# fpga01-serdes-power.net
KiCad netlist of a schematic drawn in Altium Designer
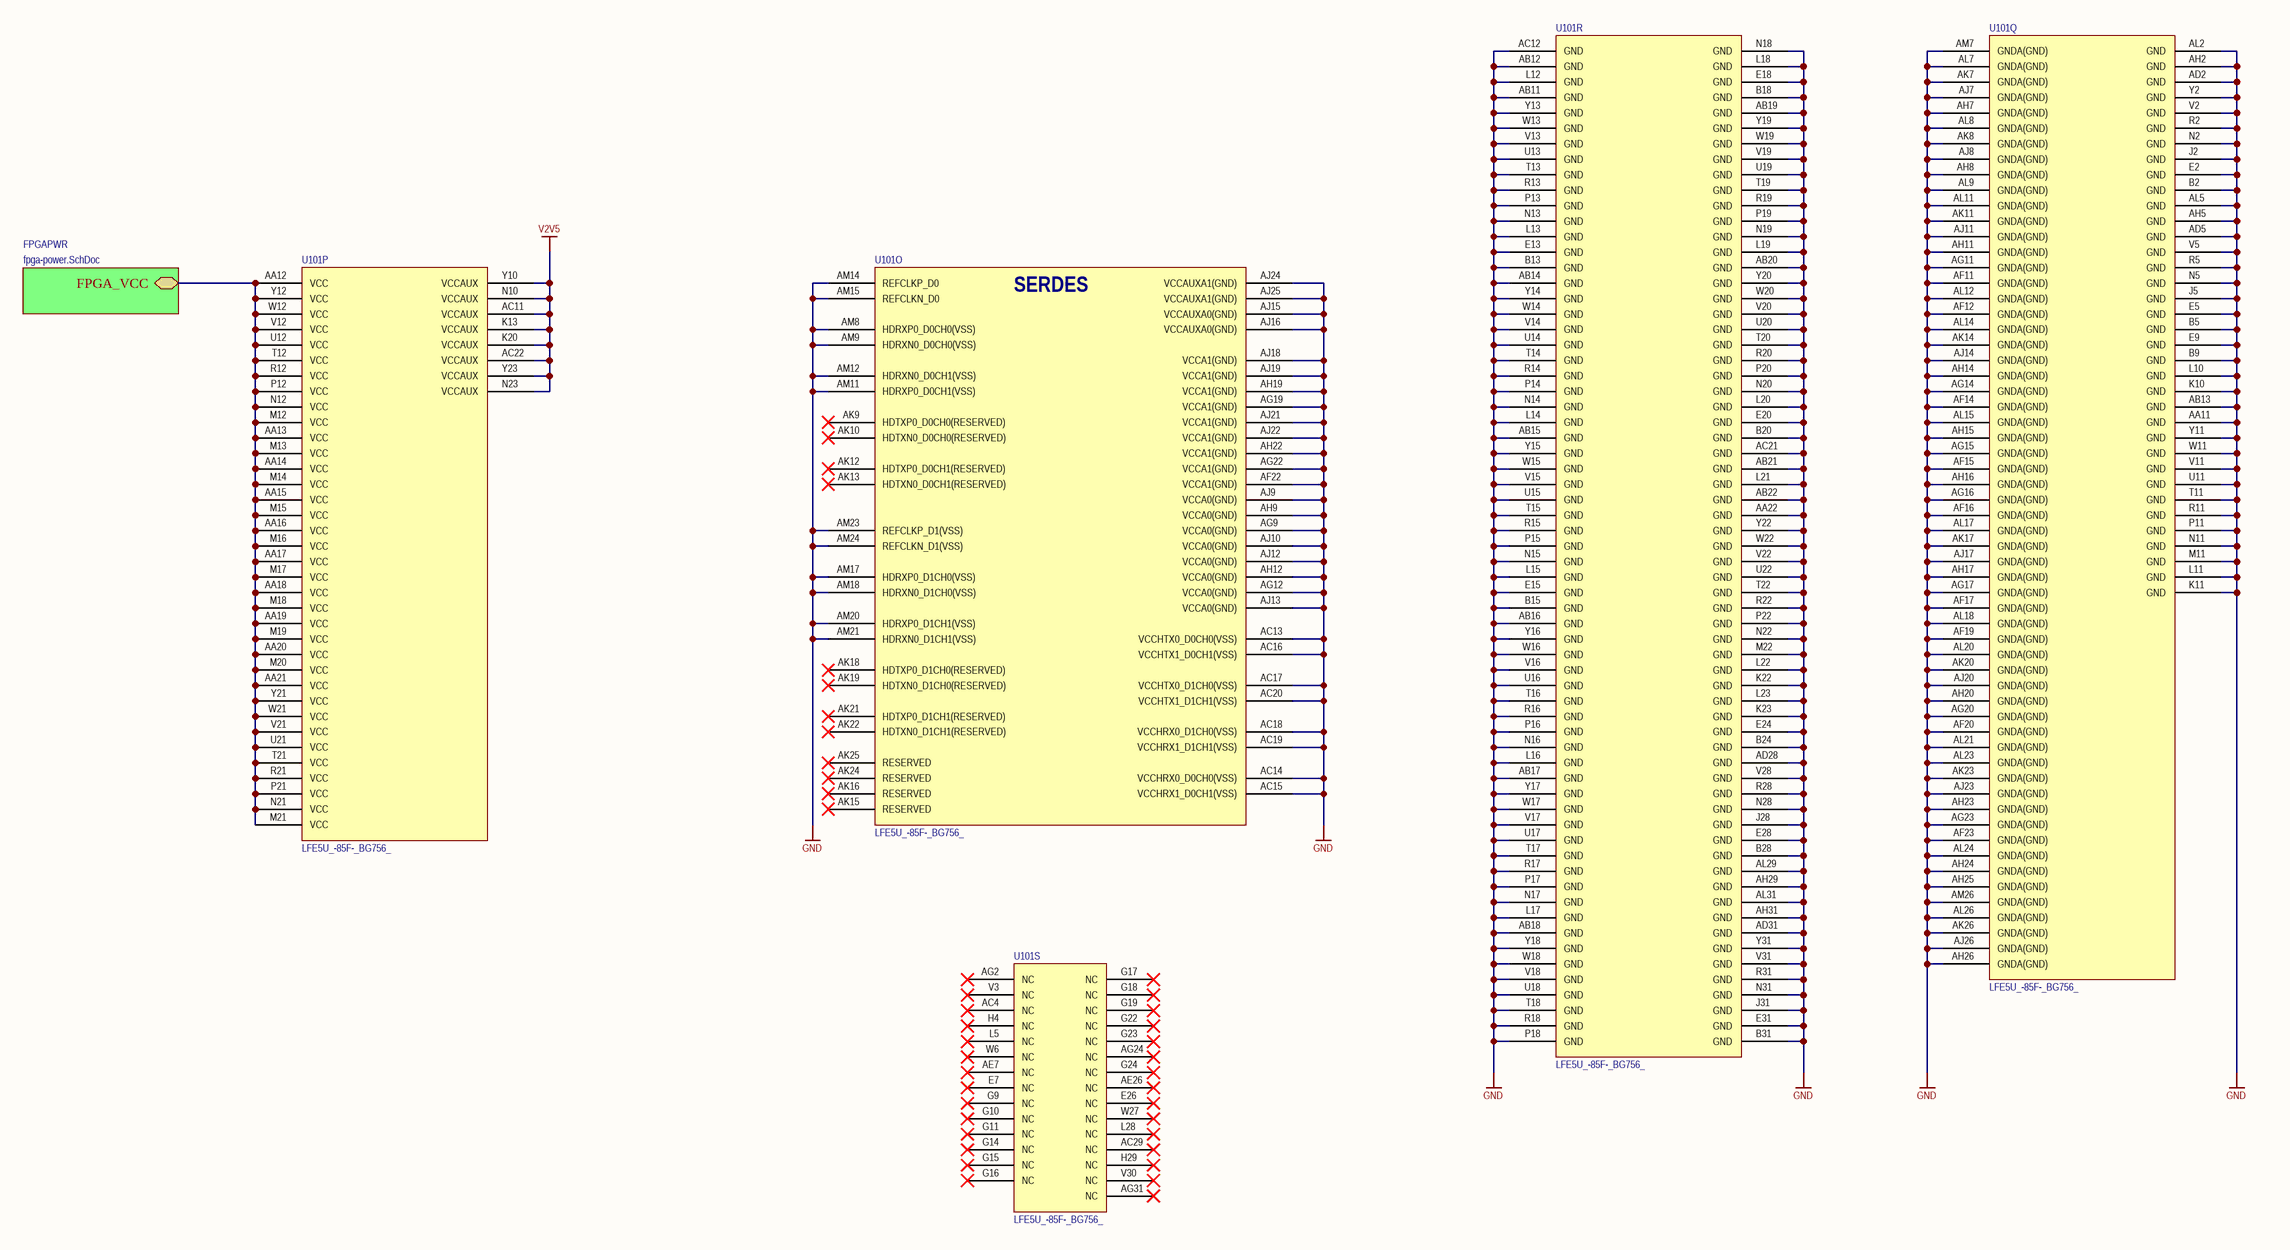
[diagram p0: fpga01-serdes-power.SchDoc]

(export (version "E")
  (design (tool "Eeschema 10.0.6"))
  (components
    (comp (ref "U101")
      (value "LFE5U_-85F-_BG756_")
      (footprint "lattice:caBGA756")
      (description "ECP5 FPGA, 85k LUT, 756-caBGA")
      (fields (field (name "MANUFACTURER") "Lattice Semiconductor"))
      (libsource (lib "lattice") (part "LFE5U_-85F-_BG756_"))
    )
  )
  (nets
    (net (code "1") (name "/FPGA_VCC") (class "Default")
      (node (ref "U101") (pin "AA12") (pinfunction "VCC_AA12") (pintype "power_in"))
      (node (ref "U101") (pin "AA13") (pinfunction "VCC_AA13") (pintype "power_in"))
      (node (ref "U101") (pin "AA14") (pinfunction "VCC_AA14") (pintype "power_in"))
      (node (ref "U101") (pin "AA15") (pinfunction "VCC_AA15") (pintype "power_in"))
      (node (ref "U101") (pin "AA16") (pinfunction "VCC_AA16") (pintype "power_in"))
      (node (ref "U101") (pin "AA17") (pinfunction "VCC_AA17") (pintype "power_in"))
      (node (ref "U101") (pin "AA18") (pinfunction "VCC_AA18") (pintype "power_in"))
      (node (ref "U101") (pin "AA19") (pinfunction "VCC_AA19") (pintype "power_in"))
      (node (ref "U101") (pin "AA20") (pinfunction "VCC_AA20") (pintype "power_in"))
      (node (ref "U101") (pin "AA21") (pinfunction "VCC_AA21") (pintype "power_in"))
      (node (ref "U101") (pin "M12") (pinfunction "VCC_M12") (pintype "power_in"))
      (node (ref "U101") (pin "M13") (pinfunction "VCC_M13") (pintype "power_in"))
      (node (ref "U101") (pin "M14") (pinfunction "VCC_M14") (pintype "power_in"))
      (node (ref "U101") (pin "M15") (pinfunction "VCC_M15") (pintype "power_in"))
      (node (ref "U101") (pin "M16") (pinfunction "VCC_M16") (pintype "power_in"))
      (node (ref "U101") (pin "M17") (pinfunction "VCC_M17") (pintype "power_in"))
      (node (ref "U101") (pin "M18") (pinfunction "VCC_M18") (pintype "power_in"))
      (node (ref "U101") (pin "M19") (pinfunction "VCC_M19") (pintype "power_in"))
      (node (ref "U101") (pin "M20") (pinfunction "VCC_M20") (pintype "power_in"))
      (node (ref "U101") (pin "M21") (pinfunction "VCC_M21") (pintype "power_in"))
      (node (ref "U101") (pin "N12") (pinfunction "VCC_N12") (pintype "power_in"))
      (node (ref "U101") (pin "N21") (pinfunction "VCC_N21") (pintype "power_in"))
      (node (ref "U101") (pin "P12") (pinfunction "VCC_P12") (pintype "power_in"))
      (node (ref "U101") (pin "P21") (pinfunction "VCC_P21") (pintype "power_in"))
      (node (ref "U101") (pin "R12") (pinfunction "VCC_R12") (pintype "power_in"))
      (node (ref "U101") (pin "R21") (pinfunction "VCC_R21") (pintype "power_in"))
      (node (ref "U101") (pin "T12") (pinfunction "VCC_T12") (pintype "power_in"))
      (node (ref "U101") (pin "T21") (pinfunction "VCC_T21") (pintype "power_in"))
      (node (ref "U101") (pin "U12") (pinfunction "VCC_U12") (pintype "power_in"))
      (node (ref "U101") (pin "U21") (pinfunction "VCC_U21") (pintype "power_in"))
      (node (ref "U101") (pin "V12") (pinfunction "VCC_V12") (pintype "power_in"))
      (node (ref "U101") (pin "V21") (pinfunction "VCC_V21") (pintype "power_in"))
      (node (ref "U101") (pin "W12") (pinfunction "VCC_W12") (pintype "power_in"))
      (node (ref "U101") (pin "W21") (pinfunction "VCC_W21") (pintype "power_in"))
      (node (ref "U101") (pin "Y12") (pinfunction "VCC_Y12") (pintype "power_in"))
      (node (ref "U101") (pin "Y21") (pinfunction "VCC_Y21") (pintype "power_in"))
    )
    (net (code "2") (name "GND") (class "Default")
      (node (ref "U101") (pin "AA11") (pinfunction "GND_AA11") (pintype "power_in"))
      (node (ref "U101") (pin "AA22") (pinfunction "GND_AA22") (pintype "power_in"))
      (node (ref "U101") (pin "AB11") (pinfunction "GND_AB11") (pintype "power_in"))
      (node (ref "U101") (pin "AB12") (pinfunction "GND_AB12") (pintype "power_in"))
      (node (ref "U101") (pin "AB13") (pinfunction "GND_AB13") (pintype "power_in"))
      (node (ref "U101") (pin "AB14") (pinfunction "GND_AB14") (pintype "power_in"))
      (node (ref "U101") (pin "AB15") (pinfunction "GND_AB15") (pintype "power_in"))
      (node (ref "U101") (pin "AB16") (pinfunction "GND_AB16") (pintype "power_in"))
      (node (ref "U101") (pin "AB17") (pinfunction "GND_AB17") (pintype "power_in"))
      (node (ref "U101") (pin "AB18") (pinfunction "GND_AB18") (pintype "power_in"))
      (node (ref "U101") (pin "AB19") (pinfunction "GND_AB19") (pintype "power_in"))
      (node (ref "U101") (pin "AB20") (pinfunction "GND_AB20") (pintype "power_in"))
      (node (ref "U101") (pin "AB21") (pinfunction "GND_AB21") (pintype "power_in"))
      (node (ref "U101") (pin "AB22") (pinfunction "GND_AB22") (pintype "power_in"))
      (node (ref "U101") (pin "AC12") (pinfunction "GND_AC12") (pintype "power_in"))
      (node (ref "U101") (pin "AC13") (pinfunction "VCCHTX0_D0CH0(VSS)_AC13") (pintype "power_in"))
      (node (ref "U101") (pin "AC14") (pinfunction "VCCHRX0_D0CH0(VSS)_AC14") (pintype "power_in"))
      (node (ref "U101") (pin "AC15") (pinfunction "VCCHRX1_D0CH1(VSS)_AC15") (pintype "power_in"))
      (node (ref "U101") (pin "AC16") (pinfunction "VCCHTX1_D0CH1(VSS)_AC16") (pintype "power_in"))
      (node (ref "U101") (pin "AC17") (pinfunction "VCCHTX0_D1CH0(VSS)_AC17") (pintype "power_in"))
      (node (ref "U101") (pin "AC18") (pinfunction "VCCHRX0_D1CH0(VSS)_AC18") (pintype "power_in"))
      (node (ref "U101") (pin "AC19") (pinfunction "VCCHRX1_D1CH1(VSS)_AC19") (pintype "power_in"))
      (node (ref "U101") (pin "AC20") (pinfunction "VCCHTX1_D1CH1(VSS)_AC20") (pintype "power_in"))
      (node (ref "U101") (pin "AC21") (pinfunction "GND_AC21") (pintype "power_in"))
      (node (ref "U101") (pin "AD2") (pinfunction "GND_AD2") (pintype "power_in"))
      (node (ref "U101") (pin "AD28") (pinfunction "GND_AD28") (pintype "power_in"))
      (node (ref "U101") (pin "AD31") (pinfunction "GND_AD31") (pintype "power_in"))
      (node (ref "U101") (pin "AD5") (pinfunction "GND_AD5") (pintype "power_in"))
      (node (ref "U101") (pin "AF11") (pinfunction "GNDA(GND)_AF11") (pintype "power_in"))
      (node (ref "U101") (pin "AF12") (pinfunction "GNDA(GND)_AF12") (pintype "power_in"))
      (node (ref "U101") (pin "AF14") (pinfunction "GNDA(GND)_AF14") (pintype "power_in"))
      (node (ref "U101") (pin "AF15") (pinfunction "GNDA(GND)_AF15") (pintype "power_in"))
      (node (ref "U101") (pin "AF16") (pinfunction "GNDA(GND)_AF16") (pintype "power_in"))
      (node (ref "U101") (pin "AF17") (pinfunction "GNDA(GND)_AF17") (pintype "power_in"))
      (node (ref "U101") (pin "AF19") (pinfunction "GNDA(GND)_AF19") (pintype "power_in"))
      (node (ref "U101") (pin "AF20") (pinfunction "GNDA(GND)_AF20") (pintype "power_in"))
      (node (ref "U101") (pin "AF22") (pinfunction "VCCA1(GND)_AF22") (pintype "power_in"))
      (node (ref "U101") (pin "AF23") (pinfunction "GNDA(GND)_AF23") (pintype "power_in"))
      (node (ref "U101") (pin "AG11") (pinfunction "GNDA(GND)_AG11") (pintype "power_in"))
      (node (ref "U101") (pin "AG12") (pinfunction "VCCA0(GND)_AG12") (pintype "power_in"))
      (node (ref "U101") (pin "AG14") (pinfunction "GNDA(GND)_AG14") (pintype "power_in"))
      (node (ref "U101") (pin "AG15") (pinfunction "GNDA(GND)_AG15") (pintype "power_in"))
      (node (ref "U101") (pin "AG16") (pinfunction "GNDA(GND)_AG16") (pintype "power_in"))
      (node (ref "U101") (pin "AG17") (pinfunction "GNDA(GND)_AG17") (pintype "power_in"))
      (node (ref "U101") (pin "AG19") (pinfunction "VCCA1(GND)_AG19") (pintype "power_in"))
      (node (ref "U101") (pin "AG20") (pinfunction "GNDA(GND)_AG20") (pintype "power_in"))
      (node (ref "U101") (pin "AG22") (pinfunction "VCCA1(GND)_AG22") (pintype "power_in"))
      (node (ref "U101") (pin "AG23") (pinfunction "GNDA(GND)_AG23") (pintype "power_in"))
      (node (ref "U101") (pin "AG9") (pinfunction "VCCA0(GND)_AG9") (pintype "power_in"))
      (node (ref "U101") (pin "AH11") (pinfunction "GNDA(GND)_AH11") (pintype "power_in"))
      (node (ref "U101") (pin "AH12") (pinfunction "VCCA0(GND)_AH12") (pintype "power_in"))
      (node (ref "U101") (pin "AH14") (pinfunction "GNDA(GND)_AH14") (pintype "power_in"))
      (node (ref "U101") (pin "AH15") (pinfunction "GNDA(GND)_AH15") (pintype "power_in"))
      (node (ref "U101") (pin "AH16") (pinfunction "GNDA(GND)_AH16") (pintype "power_in"))
      (node (ref "U101") (pin "AH17") (pinfunction "GNDA(GND)_AH17") (pintype "power_in"))
      (node (ref "U101") (pin "AH19") (pinfunction "VCCA1(GND)_AH19") (pintype "power_in"))
      (node (ref "U101") (pin "AH2") (pinfunction "GND_AH2") (pintype "power_in"))
      (node (ref "U101") (pin "AH20") (pinfunction "GNDA(GND)_AH20") (pintype "power_in"))
      (node (ref "U101") (pin "AH22") (pinfunction "VCCA1(GND)_AH22") (pintype "power_in"))
      (node (ref "U101") (pin "AH23") (pinfunction "GNDA(GND)_AH23") (pintype "power_in"))
      (node (ref "U101") (pin "AH24") (pinfunction "GNDA(GND)_AH24") (pintype "power_in"))
      (node (ref "U101") (pin "AH25") (pinfunction "GNDA(GND)_AH25") (pintype "power_in"))
      (node (ref "U101") (pin "AH26") (pinfunction "GNDA(GND)_AH26") (pintype "power_in"))
      (node (ref "U101") (pin "AH29") (pinfunction "GND_AH29") (pintype "power_in"))
      (node (ref "U101") (pin "AH31") (pinfunction "GND_AH31") (pintype "power_in"))
      (node (ref "U101") (pin "AH5") (pinfunction "GND_AH5") (pintype "power_in"))
      (node (ref "U101") (pin "AH7") (pinfunction "GNDA(GND)_AH7") (pintype "power_in"))
      (node (ref "U101") (pin "AH8") (pinfunction "GNDA(GND)_AH8") (pintype "power_in"))
      (node (ref "U101") (pin "AH9") (pinfunction "VCCA0(GND)_AH9") (pintype "power_in"))
      (node (ref "U101") (pin "AJ10") (pinfunction "VCCA0(GND)_AJ10") (pintype "power_in"))
      (node (ref "U101") (pin "AJ11") (pinfunction "GNDA(GND)_AJ11") (pintype "power_in"))
      (node (ref "U101") (pin "AJ12") (pinfunction "VCCA0(GND)_AJ12") (pintype "power_in"))
      (node (ref "U101") (pin "AJ13") (pinfunction "VCCA0(GND)_AJ13") (pintype "power_in"))
      (node (ref "U101") (pin "AJ14") (pinfunction "GNDA(GND)_AJ14") (pintype "power_in"))
      (node (ref "U101") (pin "AJ15") (pinfunction "VCCAUXA0(GND)_AJ15") (pintype "power_in"))
      (node (ref "U101") (pin "AJ16") (pinfunction "VCCAUXA0(GND)_AJ16") (pintype "power_in"))
      (node (ref "U101") (pin "AJ17") (pinfunction "GNDA(GND)_AJ17") (pintype "power_in"))
      (node (ref "U101") (pin "AJ18") (pinfunction "VCCA1(GND)_AJ18") (pintype "power_in"))
      (node (ref "U101") (pin "AJ19") (pinfunction "VCCA1(GND)_AJ19") (pintype "power_in"))
      (node (ref "U101") (pin "AJ20") (pinfunction "GNDA(GND)_AJ20") (pintype "power_in"))
      (node (ref "U101") (pin "AJ21") (pinfunction "VCCA1(GND)_AJ21") (pintype "power_in"))
      (node (ref "U101") (pin "AJ22") (pinfunction "VCCA1(GND)_AJ22") (pintype "power_in"))
      (node (ref "U101") (pin "AJ23") (pinfunction "GNDA(GND)_AJ23") (pintype "power_in"))
      (node (ref "U101") (pin "AJ24") (pinfunction "VCCAUXA1(GND)_AJ24") (pintype "power_in"))
      (node (ref "U101") (pin "AJ25") (pinfunction "VCCAUXA1(GND)_AJ25") (pintype "power_in"))
      (node (ref "U101") (pin "AJ26") (pinfunction "GNDA(GND)_AJ26") (pintype "power_in"))
      (node (ref "U101") (pin "AJ7") (pinfunction "GNDA(GND)_AJ7") (pintype "power_in"))
      (node (ref "U101") (pin "AJ8") (pinfunction "GNDA(GND)_AJ8") (pintype "power_in"))
      (node (ref "U101") (pin "AJ9") (pinfunction "VCCA0(GND)_AJ9") (pintype "power_in"))
      (node (ref "U101") (pin "AK11") (pinfunction "GNDA(GND)_AK11") (pintype "power_in"))
      (node (ref "U101") (pin "AK14") (pinfunction "GNDA(GND)_AK14") (pintype "power_in"))
      (node (ref "U101") (pin "AK17") (pinfunction "GNDA(GND)_AK17") (pintype "power_in"))
      (node (ref "U101") (pin "AK20") (pinfunction "GNDA(GND)_AK20") (pintype "power_in"))
      (node (ref "U101") (pin "AK23") (pinfunction "GNDA(GND)_AK23") (pintype "power_in"))
      (node (ref "U101") (pin "AK26") (pinfunction "GNDA(GND)_AK26") (pintype "power_in"))
      (node (ref "U101") (pin "AK7") (pinfunction "GNDA(GND)_AK7") (pintype "power_in"))
      (node (ref "U101") (pin "AK8") (pinfunction "GNDA(GND)_AK8") (pintype "power_in"))
      (node (ref "U101") (pin "AL11") (pinfunction "GNDA(GND)_AL11") (pintype "power_in"))
      (node (ref "U101") (pin "AL12") (pinfunction "GNDA(GND)_AL12") (pintype "power_in"))
      (node (ref "U101") (pin "AL14") (pinfunction "GNDA(GND)_AL14") (pintype "power_in"))
      (node (ref "U101") (pin "AL15") (pinfunction "GNDA(GND)_AL15") (pintype "power_in"))
      (node (ref "U101") (pin "AL17") (pinfunction "GNDA(GND)_AL17") (pintype "power_in"))
      (node (ref "U101") (pin "AL18") (pinfunction "GNDA(GND)_AL18") (pintype "power_in"))
      (node (ref "U101") (pin "AL2") (pinfunction "GND_AL2") (pintype "power_in"))
      (node (ref "U101") (pin "AL20") (pinfunction "GNDA(GND)_AL20") (pintype "power_in"))
      (node (ref "U101") (pin "AL21") (pinfunction "GNDA(GND)_AL21") (pintype "power_in"))
      (node (ref "U101") (pin "AL23") (pinfunction "GNDA(GND)_AL23") (pintype "power_in"))
      (node (ref "U101") (pin "AL24") (pinfunction "GNDA(GND)_AL24") (pintype "power_in"))
      (node (ref "U101") (pin "AL26") (pinfunction "GNDA(GND)_AL26") (pintype "power_in"))
      (node (ref "U101") (pin "AL29") (pinfunction "GND_AL29") (pintype "power_in"))
      (node (ref "U101") (pin "AL31") (pinfunction "GND_AL31") (pintype "power_in"))
      (node (ref "U101") (pin "AL5") (pinfunction "GND_AL5") (pintype "power_in"))
      (node (ref "U101") (pin "AL7") (pinfunction "GNDA(GND)_AL7") (pintype "power_in"))
      (node (ref "U101") (pin "AL8") (pinfunction "GNDA(GND)_AL8") (pintype "power_in"))
      (node (ref "U101") (pin "AL9") (pinfunction "GNDA(GND)_AL9") (pintype "power_in"))
      (node (ref "U101") (pin "AM11") (pinfunction "HDRXP0_D0CH1(VSS)_AM11") (pintype "passive"))
      (node (ref "U101") (pin "AM12") (pinfunction "HDRXN0_D0CH1(VSS)_AM12") (pintype "passive"))
      (node (ref "U101") (pin "AM14") (pinfunction "REFCLKP_D0_AM14") (pintype "passive"))
      (node (ref "U101") (pin "AM15") (pinfunction "REFCLKN_D0_AM15") (pintype "passive"))
      (node (ref "U101") (pin "AM17") (pinfunction "HDRXP0_D1CH0(VSS)_AM17") (pintype "passive"))
      (node (ref "U101") (pin "AM18") (pinfunction "HDRXN0_D1CH0(VSS)_AM18") (pintype "passive"))
      (node (ref "U101") (pin "AM20") (pinfunction "HDRXP0_D1CH1(VSS)_AM20") (pintype "passive"))
      (node (ref "U101") (pin "AM21") (pinfunction "HDRXN0_D1CH1(VSS)_AM21") (pintype "passive"))
      (node (ref "U101") (pin "AM23") (pinfunction "REFCLKP_D1(VSS)_AM23") (pintype "passive"))
      (node (ref "U101") (pin "AM24") (pinfunction "REFCLKN_D1(VSS)_AM24") (pintype "passive"))
      (node (ref "U101") (pin "AM26") (pinfunction "GNDA(GND)_AM26") (pintype "power_in"))
      (node (ref "U101") (pin "AM7") (pinfunction "GNDA(GND)_AM7") (pintype "power_in"))
      (node (ref "U101") (pin "AM8") (pinfunction "HDRXP0_D0CH0(VSS)_AM8") (pintype "passive"))
      (node (ref "U101") (pin "AM9") (pinfunction "HDRXN0_D0CH0(VSS)_AM9") (pintype "passive"))
      (node (ref "U101") (pin "B13") (pinfunction "GND_B13") (pintype "power_in"))
      (node (ref "U101") (pin "B15") (pinfunction "GND_B15") (pintype "power_in"))
      (node (ref "U101") (pin "B18") (pinfunction "GND_B18") (pintype "power_in"))
      (node (ref "U101") (pin "B2") (pinfunction "GND_B2") (pintype "power_in"))
      (node (ref "U101") (pin "B20") (pinfunction "GND_B20") (pintype "power_in"))
      (node (ref "U101") (pin "B24") (pinfunction "GND_B24") (pintype "power_in"))
      (node (ref "U101") (pin "B28") (pinfunction "GND_B28") (pintype "power_in"))
      (node (ref "U101") (pin "B31") (pinfunction "GND_B31") (pintype "power_in"))
      (node (ref "U101") (pin "B5") (pinfunction "GND_B5") (pintype "power_in"))
      (node (ref "U101") (pin "B9") (pinfunction "GND_B9") (pintype "power_in"))
      (node (ref "U101") (pin "E13") (pinfunction "GND_E13") (pintype "power_in"))
      (node (ref "U101") (pin "E15") (pinfunction "GND_E15") (pintype "power_in"))
      (node (ref "U101") (pin "E18") (pinfunction "GND_E18") (pintype "power_in"))
      (node (ref "U101") (pin "E2") (pinfunction "GND_E2") (pintype "power_in"))
      (node (ref "U101") (pin "E20") (pinfunction "GND_E20") (pintype "power_in"))
      (node (ref "U101") (pin "E24") (pinfunction "GND_E24") (pintype "power_in"))
      (node (ref "U101") (pin "E28") (pinfunction "GND_E28") (pintype "power_in"))
      (node (ref "U101") (pin "E31") (pinfunction "GND_E31") (pintype "power_in"))
      (node (ref "U101") (pin "E5") (pinfunction "GND_E5") (pintype "power_in"))
      (node (ref "U101") (pin "E9") (pinfunction "GND_E9") (pintype "power_in"))
      (node (ref "U101") (pin "J2") (pinfunction "GND_J2") (pintype "power_in"))
      (node (ref "U101") (pin "J28") (pinfunction "GND_J28") (pintype "power_in"))
      (node (ref "U101") (pin "J31") (pinfunction "GND_J31") (pintype "power_in"))
      (node (ref "U101") (pin "J5") (pinfunction "GND_J5") (pintype "power_in"))
      (node (ref "U101") (pin "K10") (pinfunction "GND_K10") (pintype "power_in"))
      (node (ref "U101") (pin "K11") (pinfunction "GND_K11") (pintype "power_in"))
      (node (ref "U101") (pin "K22") (pinfunction "GND_K22") (pintype "power_in"))
      (node (ref "U101") (pin "K23") (pinfunction "GND_K23") (pintype "power_in"))
      (node (ref "U101") (pin "L10") (pinfunction "GND_L10") (pintype "power_in"))
      (node (ref "U101") (pin "L11") (pinfunction "GND_L11") (pintype "power_in"))
      (node (ref "U101") (pin "L12") (pinfunction "GND_L12") (pintype "power_in"))
      (node (ref "U101") (pin "L13") (pinfunction "GND_L13") (pintype "power_in"))
      (node (ref "U101") (pin "L14") (pinfunction "GND_L14") (pintype "power_in"))
      (node (ref "U101") (pin "L15") (pinfunction "GND_L15") (pintype "power_in"))
      (node (ref "U101") (pin "L16") (pinfunction "GND_L16") (pintype "power_in"))
      (node (ref "U101") (pin "L17") (pinfunction "GND_L17") (pintype "power_in"))
      (node (ref "U101") (pin "L18") (pinfunction "GND_L18") (pintype "power_in"))
      (node (ref "U101") (pin "L19") (pinfunction "GND_L19") (pintype "power_in"))
      (node (ref "U101") (pin "L20") (pinfunction "GND_L20") (pintype "power_in"))
      (node (ref "U101") (pin "L21") (pinfunction "GND_L21") (pintype "power_in"))
      (node (ref "U101") (pin "L22") (pinfunction "GND_L22") (pintype "power_in"))
      (node (ref "U101") (pin "L23") (pinfunction "GND_L23") (pintype "power_in"))
      (node (ref "U101") (pin "M11") (pinfunction "GND_M11") (pintype "power_in"))
      (node (ref "U101") (pin "M22") (pinfunction "GND_M22") (pintype "power_in"))
      (node (ref "U101") (pin "N11") (pinfunction "GND_N11") (pintype "power_in"))
      (node (ref "U101") (pin "N13") (pinfunction "GND_N13") (pintype "power_in"))
      (node (ref "U101") (pin "N14") (pinfunction "GND_N14") (pintype "power_in"))
      (node (ref "U101") (pin "N15") (pinfunction "GND_N15") (pintype "power_in"))
      (node (ref "U101") (pin "N16") (pinfunction "GND_N16") (pintype "power_in"))
      (node (ref "U101") (pin "N17") (pinfunction "GND_N17") (pintype "power_in"))
      (node (ref "U101") (pin "N18") (pinfunction "GND_N18") (pintype "power_in"))
      (node (ref "U101") (pin "N19") (pinfunction "GND_N19") (pintype "power_in"))
      (node (ref "U101") (pin "N2") (pinfunction "GND_N2") (pintype "power_in"))
      (node (ref "U101") (pin "N20") (pinfunction "GND_N20") (pintype "power_in"))
      (node (ref "U101") (pin "N22") (pinfunction "GND_N22") (pintype "power_in"))
      (node (ref "U101") (pin "N28") (pinfunction "GND_N28") (pintype "power_in"))
      (node (ref "U101") (pin "N31") (pinfunction "GND_N31") (pintype "power_in"))
      (node (ref "U101") (pin "N5") (pinfunction "GND_N5") (pintype "power_in"))
      (node (ref "U101") (pin "P11") (pinfunction "GND_P11") (pintype "power_in"))
      (node (ref "U101") (pin "P13") (pinfunction "GND_P13") (pintype "power_in"))
      (node (ref "U101") (pin "P14") (pinfunction "GND_P14") (pintype "power_in"))
      (node (ref "U101") (pin "P15") (pinfunction "GND_P15") (pintype "power_in"))
      (node (ref "U101") (pin "P16") (pinfunction "GND_P16") (pintype "power_in"))
      (node (ref "U101") (pin "P17") (pinfunction "GND_P17") (pintype "power_in"))
      (node (ref "U101") (pin "P18") (pinfunction "GND_P18") (pintype "power_in"))
      (node (ref "U101") (pin "P19") (pinfunction "GND_P19") (pintype "power_in"))
      (node (ref "U101") (pin "P20") (pinfunction "GND_P20") (pintype "power_in"))
      (node (ref "U101") (pin "P22") (pinfunction "GND_P22") (pintype "power_in"))
      (node (ref "U101") (pin "R11") (pinfunction "GND_R11") (pintype "power_in"))
      (node (ref "U101") (pin "R13") (pinfunction "GND_R13") (pintype "power_in"))
      (node (ref "U101") (pin "R14") (pinfunction "GND_R14") (pintype "power_in"))
      (node (ref "U101") (pin "R15") (pinfunction "GND_R15") (pintype "power_in"))
      (node (ref "U101") (pin "R16") (pinfunction "GND_R16") (pintype "power_in"))
      (node (ref "U101") (pin "R17") (pinfunction "GND_R17") (pintype "power_in"))
      (node (ref "U101") (pin "R18") (pinfunction "GND_R18") (pintype "power_in"))
      (node (ref "U101") (pin "R19") (pinfunction "GND_R19") (pintype "power_in"))
      (node (ref "U101") (pin "R2") (pinfunction "GND_R2") (pintype "power_in"))
      (node (ref "U101") (pin "R20") (pinfunction "GND_R20") (pintype "power_in"))
      (node (ref "U101") (pin "R22") (pinfunction "GND_R22") (pintype "power_in"))
      (node (ref "U101") (pin "R28") (pinfunction "GND_R28") (pintype "power_in"))
      (node (ref "U101") (pin "R31") (pinfunction "GND_R31") (pintype "power_in"))
      (node (ref "U101") (pin "R5") (pinfunction "GND_R5") (pintype "power_in"))
      (node (ref "U101") (pin "T11") (pinfunction "GND_T11") (pintype "power_in"))
      (node (ref "U101") (pin "T13") (pinfunction "GND_T13") (pintype "power_in"))
      (node (ref "U101") (pin "T14") (pinfunction "GND_T14") (pintype "power_in"))
      (node (ref "U101") (pin "T15") (pinfunction "GND_T15") (pintype "power_in"))
      (node (ref "U101") (pin "T16") (pinfunction "GND_T16") (pintype "power_in"))
      (node (ref "U101") (pin "T17") (pinfunction "GND_T17") (pintype "power_in"))
      (node (ref "U101") (pin "T18") (pinfunction "GND_T18") (pintype "power_in"))
      (node (ref "U101") (pin "T19") (pinfunction "GND_T19") (pintype "power_in"))
      (node (ref "U101") (pin "T20") (pinfunction "GND_T20") (pintype "power_in"))
      (node (ref "U101") (pin "T22") (pinfunction "GND_T22") (pintype "power_in"))
      (node (ref "U101") (pin "U11") (pinfunction "GND_U11") (pintype "power_in"))
      (node (ref "U101") (pin "U13") (pinfunction "GND_U13") (pintype "power_in"))
      (node (ref "U101") (pin "U14") (pinfunction "GND_U14") (pintype "power_in"))
      (node (ref "U101") (pin "U15") (pinfunction "GND_U15") (pintype "power_in"))
      (node (ref "U101") (pin "U16") (pinfunction "GND_U16") (pintype "power_in"))
      (node (ref "U101") (pin "U17") (pinfunction "GND_U17") (pintype "power_in"))
      (node (ref "U101") (pin "U18") (pinfunction "GND_U18") (pintype "power_in"))
      (node (ref "U101") (pin "U19") (pinfunction "GND_U19") (pintype "power_in"))
      (node (ref "U101") (pin "U20") (pinfunction "GND_U20") (pintype "power_in"))
      (node (ref "U101") (pin "U22") (pinfunction "GND_U22") (pintype "power_in"))
      (node (ref "U101") (pin "V11") (pinfunction "GND_V11") (pintype "power_in"))
      (node (ref "U101") (pin "V13") (pinfunction "GND_V13") (pintype "power_in"))
      (node (ref "U101") (pin "V14") (pinfunction "GND_V14") (pintype "power_in"))
      (node (ref "U101") (pin "V15") (pinfunction "GND_V15") (pintype "power_in"))
      (node (ref "U101") (pin "V16") (pinfunction "GND_V16") (pintype "power_in"))
      (node (ref "U101") (pin "V17") (pinfunction "GND_V17") (pintype "power_in"))
      (node (ref "U101") (pin "V18") (pinfunction "GND_V18") (pintype "power_in"))
      (node (ref "U101") (pin "V19") (pinfunction "GND_V19") (pintype "power_in"))
      (node (ref "U101") (pin "V2") (pinfunction "GND_V2") (pintype "power_in"))
      (node (ref "U101") (pin "V20") (pinfunction "GND_V20") (pintype "power_in"))
      (node (ref "U101") (pin "V22") (pinfunction "GND_V22") (pintype "power_in"))
      (node (ref "U101") (pin "V28") (pinfunction "GND_V28") (pintype "power_in"))
      (node (ref "U101") (pin "V31") (pinfunction "GND_V31") (pintype "power_in"))
      (node (ref "U101") (pin "V5") (pinfunction "GND_V5") (pintype "power_in"))
      (node (ref "U101") (pin "W11") (pinfunction "GND_W11") (pintype "power_in"))
      (node (ref "U101") (pin "W13") (pinfunction "GND_W13") (pintype "power_in"))
      (node (ref "U101") (pin "W14") (pinfunction "GND_W14") (pintype "power_in"))
      (node (ref "U101") (pin "W15") (pinfunction "GND_W15") (pintype "power_in"))
      (node (ref "U101") (pin "W16") (pinfunction "GND_W16") (pintype "power_in"))
      (node (ref "U101") (pin "W17") (pinfunction "GND_W17") (pintype "power_in"))
      (node (ref "U101") (pin "W18") (pinfunction "GND_W18") (pintype "power_in"))
      (node (ref "U101") (pin "W19") (pinfunction "GND_W19") (pintype "power_in"))
      (node (ref "U101") (pin "W20") (pinfunction "GND_W20") (pintype "power_in"))
      (node (ref "U101") (pin "W22") (pinfunction "GND_W22") (pintype "power_in"))
      (node (ref "U101") (pin "Y11") (pinfunction "GND_Y11") (pintype "power_in"))
      (node (ref "U101") (pin "Y13") (pinfunction "GND_Y13") (pintype "power_in"))
      (node (ref "U101") (pin "Y14") (pinfunction "GND_Y14") (pintype "power_in"))
      (node (ref "U101") (pin "Y15") (pinfunction "GND_Y15") (pintype "power_in"))
      (node (ref "U101") (pin "Y16") (pinfunction "GND_Y16") (pintype "power_in"))
      (node (ref "U101") (pin "Y17") (pinfunction "GND_Y17") (pintype "power_in"))
      (node (ref "U101") (pin "Y18") (pinfunction "GND_Y18") (pintype "power_in"))
      (node (ref "U101") (pin "Y19") (pinfunction "GND_Y19") (pintype "power_in"))
      (node (ref "U101") (pin "Y2") (pinfunction "GND_Y2") (pintype "power_in"))
      (node (ref "U101") (pin "Y20") (pinfunction "GND_Y20") (pintype "power_in"))
      (node (ref "U101") (pin "Y22") (pinfunction "GND_Y22") (pintype "power_in"))
      (node (ref "U101") (pin "Y31") (pinfunction "GND_Y31") (pintype "power_in"))
    )
    (net (code "3") (name "V2V5") (class "Default")
      (node (ref "U101") (pin "AC11") (pinfunction "VCCAUX_AC11") (pintype "power_in"))
      (node (ref "U101") (pin "AC22") (pinfunction "VCCAUX_AC22") (pintype "power_in"))
      (node (ref "U101") (pin "K13") (pinfunction "VCCAUX_K13") (pintype "power_in"))
      (node (ref "U101") (pin "K20") (pinfunction "VCCAUX_K20") (pintype "power_in"))
      (node (ref "U101") (pin "N10") (pinfunction "VCCAUX_N10") (pintype "power_in"))
      (node (ref "U101") (pin "N23") (pinfunction "VCCAUX_N23") (pintype "power_in"))
      (node (ref "U101") (pin "Y10") (pinfunction "VCCAUX_Y10") (pintype "power_in"))
      (node (ref "U101") (pin "Y23") (pinfunction "VCCAUX_Y23") (pintype "power_in"))
    )
    (net (code "4") (name "unconnected-(U101O-HDTXN0_D0CH0(RESERVED)-PadAK10)") (class "Default")
      (node (ref "U101") (pin "AK10") (pinfunction "HDTXN0_D0CH0(RESERVED)_AK10") (pintype "passive+no_connect"))
    )
    (net (code "5") (name "unconnected-(U101O-HDTXN0_D0CH1(RESERVED)-PadAK13)") (class "Default")
      (node (ref "U101") (pin "AK13") (pinfunction "HDTXN0_D0CH1(RESERVED)_AK13") (pintype "passive+no_connect"))
    )
    (net (code "6") (name "unconnected-(U101O-HDTXN0_D1CH0(RESERVED)-PadAK19)") (class "Default")
      (node (ref "U101") (pin "AK19") (pinfunction "HDTXN0_D1CH0(RESERVED)_AK19") (pintype "passive+no_connect"))
    )
    (net (code "7") (name "unconnected-(U101O-HDTXN0_D1CH1(RESERVED)-PadAK22)") (class "Default")
      (node (ref "U101") (pin "AK22") (pinfunction "HDTXN0_D1CH1(RESERVED)_AK22") (pintype "passive+no_connect"))
    )
    (net (code "8") (name "unconnected-(U101O-HDTXP0_D0CH0(RESERVED)-PadAK9)") (class "Default")
      (node (ref "U101") (pin "AK9") (pinfunction "HDTXP0_D0CH0(RESERVED)_AK9") (pintype "passive+no_connect"))
    )
    (net (code "9") (name "unconnected-(U101O-HDTXP0_D0CH1(RESERVED)-PadAK12)") (class "Default")
      (node (ref "U101") (pin "AK12") (pinfunction "HDTXP0_D0CH1(RESERVED)_AK12") (pintype "passive+no_connect"))
    )
    (net (code "10") (name "unconnected-(U101O-HDTXP0_D1CH0(RESERVED)-PadAK18)") (class "Default")
      (node (ref "U101") (pin "AK18") (pinfunction "HDTXP0_D1CH0(RESERVED)_AK18") (pintype "passive+no_connect"))
    )
    (net (code "11") (name "unconnected-(U101O-HDTXP0_D1CH1(RESERVED)-PadAK21)") (class "Default")
      (node (ref "U101") (pin "AK21") (pinfunction "HDTXP0_D1CH1(RESERVED)_AK21") (pintype "passive+no_connect"))
    )
    (net (code "12") (name "unconnected-(U101O-RESERVED-PadAK15)") (class "Default")
      (node (ref "U101") (pin "AK15") (pinfunction "RESERVED_AK15") (pintype "passive+no_connect"))
    )
    (net (code "13") (name "unconnected-(U101O-RESERVED-PadAK16)") (class "Default")
      (node (ref "U101") (pin "AK16") (pinfunction "RESERVED_AK16") (pintype "passive+no_connect"))
    )
    (net (code "14") (name "unconnected-(U101O-RESERVED-PadAK24)") (class "Default")
      (node (ref "U101") (pin "AK24") (pinfunction "RESERVED_AK24") (pintype "passive+no_connect"))
    )
    (net (code "15") (name "unconnected-(U101O-RESERVED-PadAK25)") (class "Default")
      (node (ref "U101") (pin "AK25") (pinfunction "RESERVED_AK25") (pintype "passive+no_connect"))
    )
    (net (code "16") (name "unconnected-(U101S-NC-PadAC4)") (class "Default")
      (node (ref "U101") (pin "AC4") (pinfunction "NC_AC4") (pintype "passive+no_connect"))
    )
    (net (code "17") (name "unconnected-(U101S-NC-PadAC29)") (class "Default")
      (node (ref "U101") (pin "AC29") (pinfunction "NC_AC29") (pintype "passive+no_connect"))
    )
    (net (code "18") (name "unconnected-(U101S-NC-PadAE7)") (class "Default")
      (node (ref "U101") (pin "AE7") (pinfunction "NC_AE7") (pintype "passive+no_connect"))
    )
    (net (code "19") (name "unconnected-(U101S-NC-PadAE26)") (class "Default")
      (node (ref "U101") (pin "AE26") (pinfunction "NC_AE26") (pintype "passive+no_connect"))
    )
    (net (code "20") (name "unconnected-(U101S-NC-PadAG2)") (class "Default")
      (node (ref "U101") (pin "AG2") (pinfunction "NC_AG2") (pintype "passive+no_connect"))
    )
    (net (code "21") (name "unconnected-(U101S-NC-PadAG24)") (class "Default")
      (node (ref "U101") (pin "AG24") (pinfunction "NC_AG24") (pintype "passive+no_connect"))
    )
    (net (code "22") (name "unconnected-(U101S-NC-PadAG31)") (class "Default")
      (node (ref "U101") (pin "AG31") (pinfunction "NC_AG31") (pintype "passive+no_connect"))
    )
    (net (code "23") (name "unconnected-(U101S-NC-PadE7)") (class "Default")
      (node (ref "U101") (pin "E7") (pinfunction "NC_E7") (pintype "passive+no_connect"))
    )
    (net (code "24") (name "unconnected-(U101S-NC-PadE26)") (class "Default")
      (node (ref "U101") (pin "E26") (pinfunction "NC_E26") (pintype "passive+no_connect"))
    )
    (net (code "25") (name "unconnected-(U101S-NC-PadG9)") (class "Default")
      (node (ref "U101") (pin "G9") (pinfunction "NC_G9") (pintype "passive+no_connect"))
    )
    (net (code "26") (name "unconnected-(U101S-NC-PadG10)") (class "Default")
      (node (ref "U101") (pin "G10") (pinfunction "NC_G10") (pintype "passive+no_connect"))
    )
    (net (code "27") (name "unconnected-(U101S-NC-PadG11)") (class "Default")
      (node (ref "U101") (pin "G11") (pinfunction "NC_G11") (pintype "passive+no_connect"))
    )
    (net (code "28") (name "unconnected-(U101S-NC-PadG14)") (class "Default")
      (node (ref "U101") (pin "G14") (pinfunction "NC_G14") (pintype "passive+no_connect"))
    )
    (net (code "29") (name "unconnected-(U101S-NC-PadG15)") (class "Default")
      (node (ref "U101") (pin "G15") (pinfunction "NC_G15") (pintype "passive+no_connect"))
    )
    (net (code "30") (name "unconnected-(U101S-NC-PadG16)") (class "Default")
      (node (ref "U101") (pin "G16") (pinfunction "NC_G16") (pintype "passive+no_connect"))
    )
    (net (code "31") (name "unconnected-(U101S-NC-PadG17)") (class "Default")
      (node (ref "U101") (pin "G17") (pinfunction "NC_G17") (pintype "passive+no_connect"))
    )
    (net (code "32") (name "unconnected-(U101S-NC-PadG18)") (class "Default")
      (node (ref "U101") (pin "G18") (pinfunction "NC_G18") (pintype "passive+no_connect"))
    )
    (net (code "33") (name "unconnected-(U101S-NC-PadG19)") (class "Default")
      (node (ref "U101") (pin "G19") (pinfunction "NC_G19") (pintype "passive+no_connect"))
    )
    (net (code "34") (name "unconnected-(U101S-NC-PadG22)") (class "Default")
      (node (ref "U101") (pin "G22") (pinfunction "NC_G22") (pintype "passive+no_connect"))
    )
    (net (code "35") (name "unconnected-(U101S-NC-PadG23)") (class "Default")
      (node (ref "U101") (pin "G23") (pinfunction "NC_G23") (pintype "passive+no_connect"))
    )
    (net (code "36") (name "unconnected-(U101S-NC-PadG24)") (class "Default")
      (node (ref "U101") (pin "G24") (pinfunction "NC_G24") (pintype "passive+no_connect"))
    )
    (net (code "37") (name "unconnected-(U101S-NC-PadH4)") (class "Default")
      (node (ref "U101") (pin "H4") (pinfunction "NC_H4") (pintype "passive+no_connect"))
    )
    (net (code "38") (name "unconnected-(U101S-NC-PadH29)") (class "Default")
      (node (ref "U101") (pin "H29") (pinfunction "NC_H29") (pintype "passive+no_connect"))
    )
    (net (code "39") (name "unconnected-(U101S-NC-PadL5)") (class "Default")
      (node (ref "U101") (pin "L5") (pinfunction "NC_L5") (pintype "passive+no_connect"))
    )
    (net (code "40") (name "unconnected-(U101S-NC-PadL28)") (class "Default")
      (node (ref "U101") (pin "L28") (pinfunction "NC_L28") (pintype "passive+no_connect"))
    )
    (net (code "41") (name "unconnected-(U101S-NC-PadV3)") (class "Default")
      (node (ref "U101") (pin "V3") (pinfunction "NC_V3") (pintype "passive+no_connect"))
    )
    (net (code "42") (name "unconnected-(U101S-NC-PadV30)") (class "Default")
      (node (ref "U101") (pin "V30") (pinfunction "NC_V30") (pintype "passive+no_connect"))
    )
    (net (code "43") (name "unconnected-(U101S-NC-PadW6)") (class "Default")
      (node (ref "U101") (pin "W6") (pinfunction "NC_W6") (pintype "passive+no_connect"))
    )
    (net (code "44") (name "unconnected-(U101S-NC-PadW27)") (class "Default")
      (node (ref "U101") (pin "W27") (pinfunction "NC_W27") (pintype "passive+no_connect"))
    )
  )
)
